# SCH_ChaserPCB_2025-10-18.net
KiCad netlist of a schematic drawn in EasyEDA
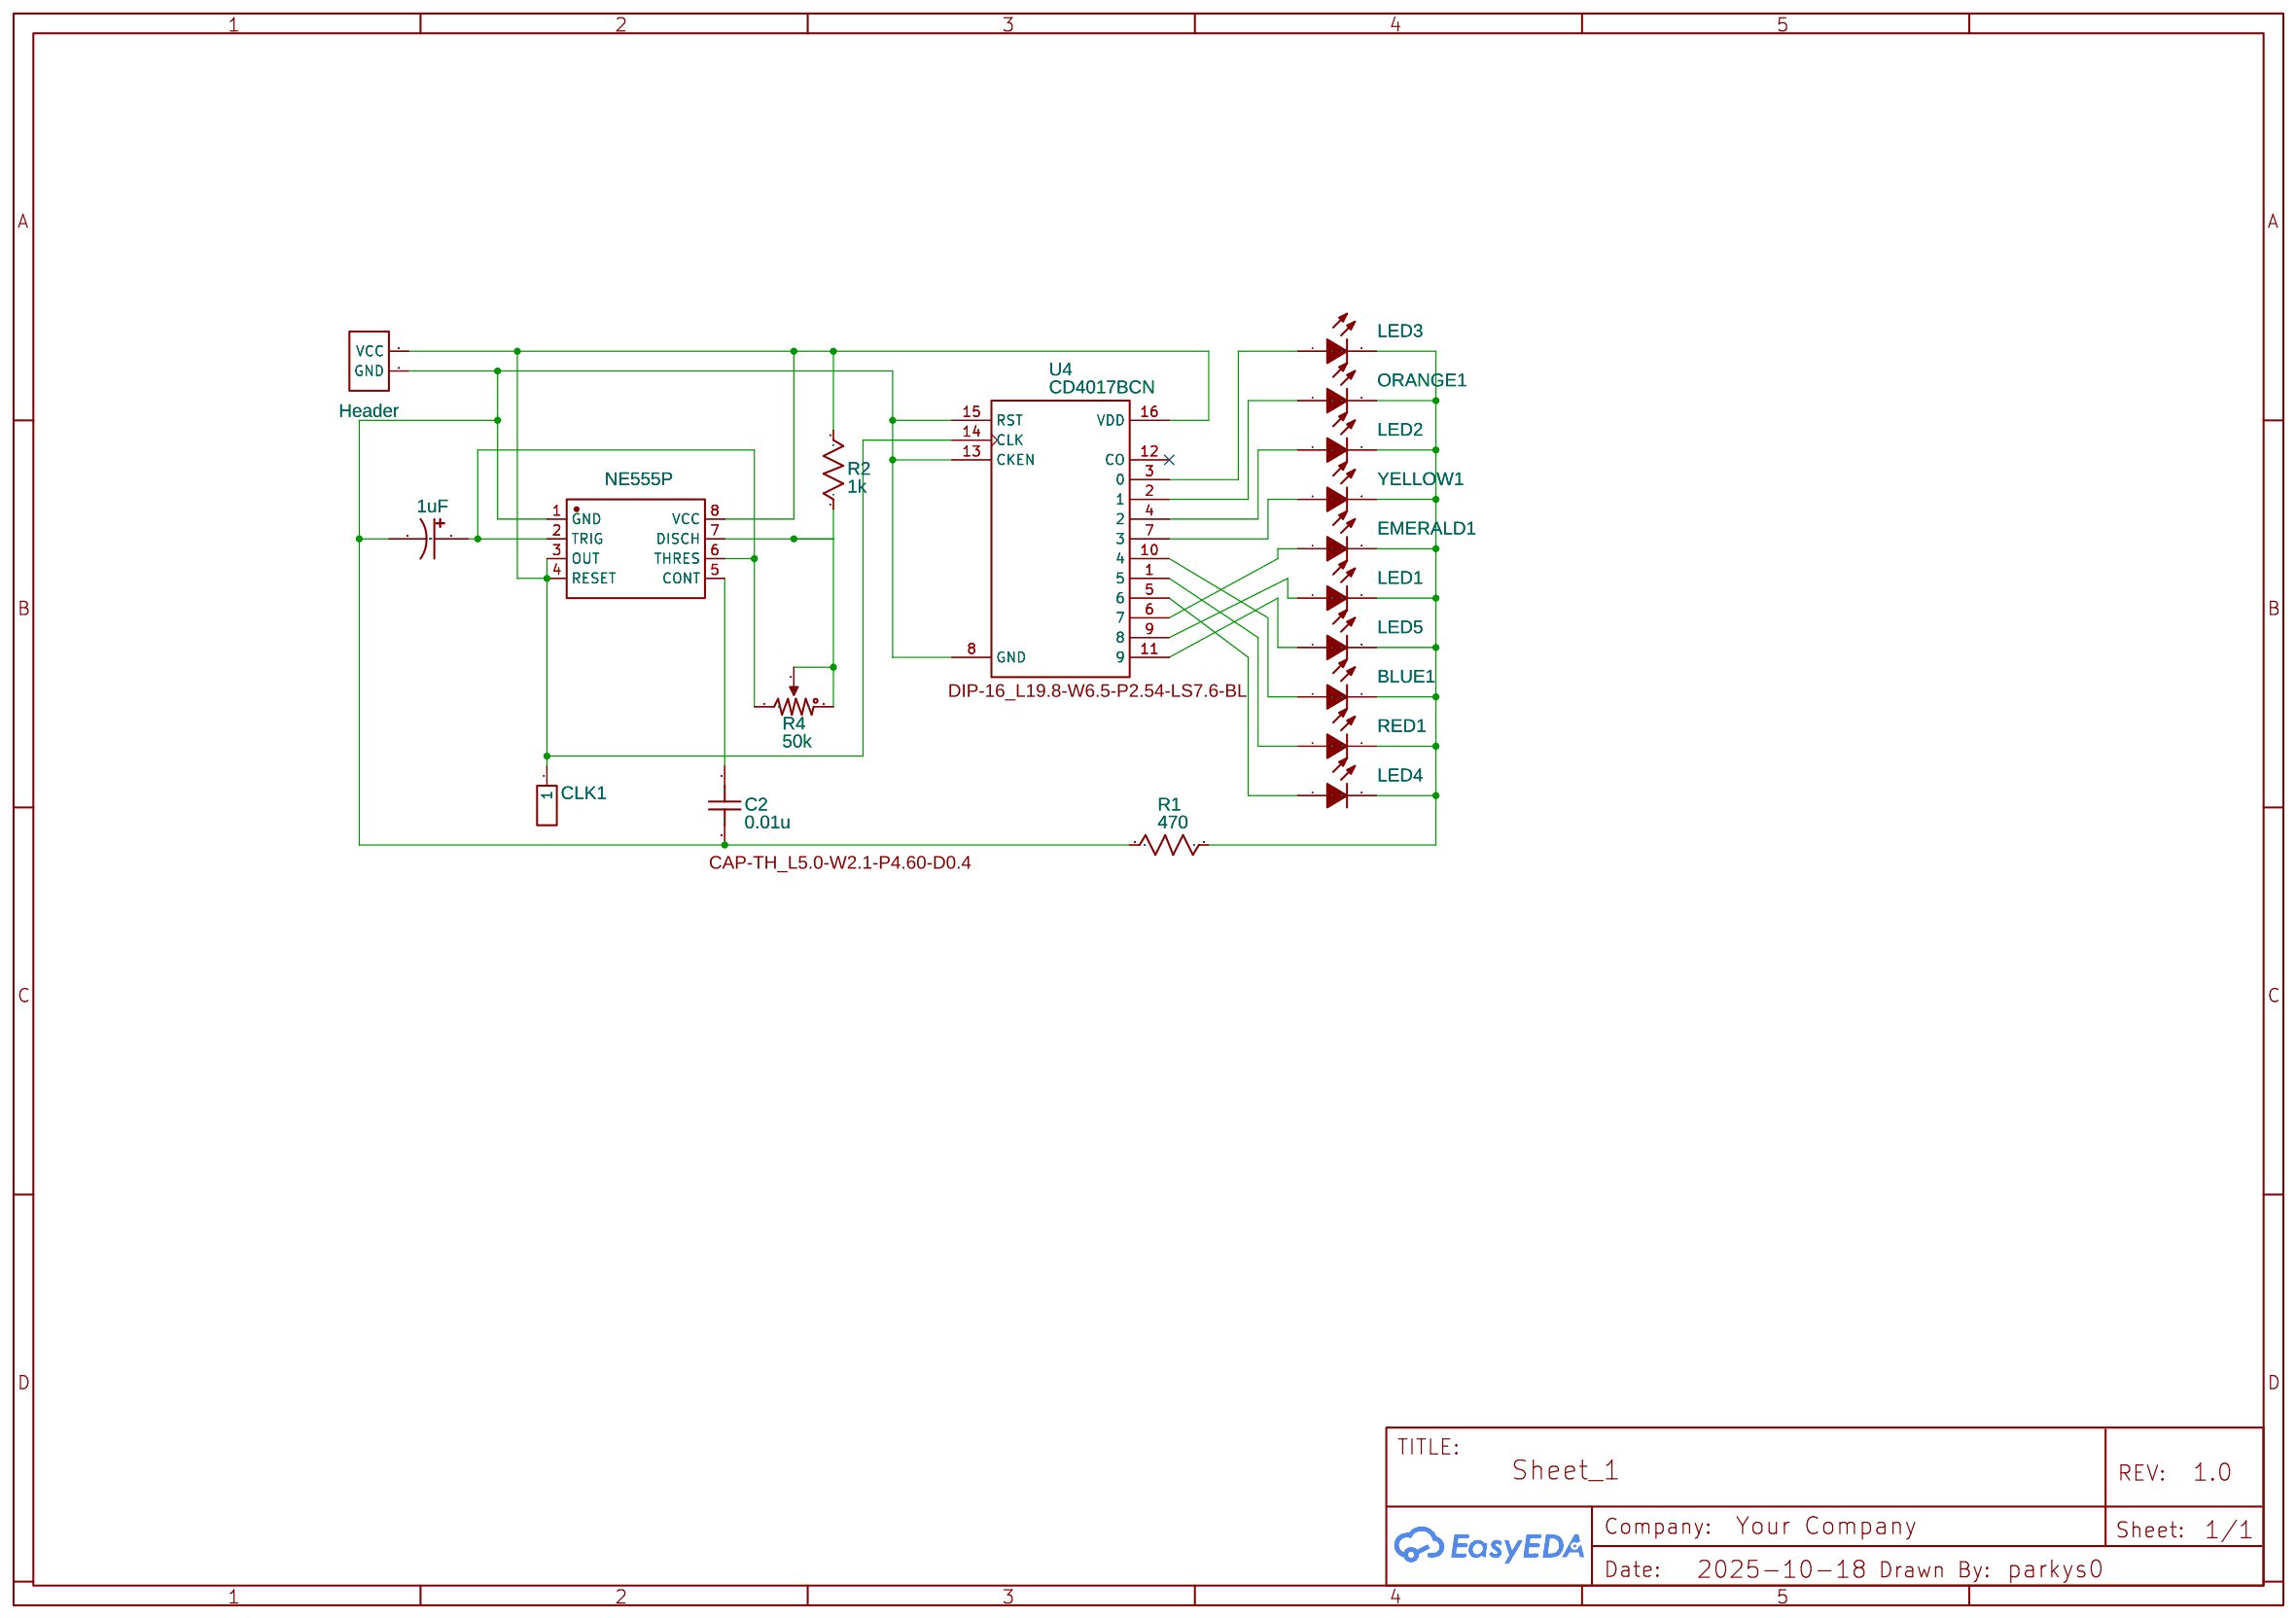
[diagram p0: schematic sheet]

(export (version "E")
  (design (tool "Eeschema 10.0.6"))
  (components
    (comp (ref "BLUE1") (value "LED_5MM") (libsource (lib "") (part "LED_5MM_1")))
    (comp (ref "C1")
      (value "1uF")
      (fields (field (name "Manufacturer Part") "UVZ1H010MDD") (field (name "Manufacturer") "Nichicon(尼吉康)"))
      (libsource (lib "") (part "UVZ1H010MDD"))
    )
    (comp (ref "C2") (value "0.01u") (libsource (lib "") (part "C_0603_US")))
    (comp (ref "CLK1")
      (value "C81276")
      (fields
        (field (name "Manufacturer Part") "2.54-1*1P针")
        (field (name "Manufacturer") "BOOMELE(Boom Precision Elec)")
      )
      (libsource (lib "") (part "Header-Male-2.54_1x1"))
    )
    (comp (ref "EMERALD1") (value "LED_5MM") (libsource (lib "") (part "LED_5MM_4")))
    (comp (ref "H1") (value "Header") (libsource (lib "") (part "HEADER-FEMALE-2.54_1X2")))
    (comp (ref "LED1") (value "LED_5MM") (libsource (lib "") (part "LED_5MM")))
    (comp (ref "LED2") (value "LED_5MM") (libsource (lib "") (part "LED_5MM")))
    (comp (ref "LED3") (value "LED_5MM") (libsource (lib "") (part "LED_5MM")))
    (comp (ref "LED4") (value "LED_5MM") (libsource (lib "") (part "LED_5MM")))
    (comp (ref "LED5") (value "LED_5MM") (libsource (lib "") (part "LED_5MM")))
    (comp (ref "ORANGE1") (value "LED_5MM") (libsource (lib "") (part "LED_5MM_5")))
    (comp (ref "R1")
      (value "470")
      (fields (field (name "Manufacturer Part") "?"))
      (libsource (lib "") (part "Resistor"))
    )
    (comp (ref "R2")
      (value "1k")
      (fields (field (name "Manufacturer Part") "?"))
      (libsource (lib "") (part "Resistor_1"))
    )
    (comp (ref "R4")
      (value "50k")
      (fields (field (name "Manufacturer Part") "?"))
      (libsource (lib "") (part "Potentiometer"))
    )
    (comp (ref "RED1") (value "LED_5MM") (libsource (lib "") (part "LED_5MM_2")))
    (comp (ref "U2")
      (value "NE555P")
      (fields (field (name "Manufacturer") "TI(德州仪器)"))
      (libsource (lib "") (part "NE555P"))
    )
    (comp (ref "U4") (value "CD4017BCN") (libsource (lib "") (part "CD4017BCN")))
    (comp (ref "YELLOW1") (value "LED_5MM") (libsource (lib "") (part "LED_5MM_3")))
  )
  (nets
    (net (code "1") (name "Net-(BLUE1-A)") (class "Default")
      (node (ref "BLUE1") (pin "1") (pinfunction "A_1") (pintype "input"))
      (node (ref "U4") (pin "10") (pinfunction "4_10") (pintype "output"))
    )
    (net (code "2") (name "Net-(BLUE1-K)") (class "Default")
      (node (ref "BLUE1") (pin "2") (pinfunction "K_2") (pintype "input"))
      (node (ref "EMERALD1") (pin "2") (pinfunction "K_2") (pintype "input"))
      (node (ref "LED1") (pin "2") (pinfunction "K_2") (pintype "input"))
      (node (ref "LED2") (pin "2") (pinfunction "K_2") (pintype "input"))
      (node (ref "LED3") (pin "2") (pinfunction "K_2") (pintype "input"))
      (node (ref "LED4") (pin "2") (pinfunction "K_2") (pintype "input"))
      (node (ref "LED5") (pin "2") (pinfunction "K_2") (pintype "input"))
      (node (ref "ORANGE1") (pin "2") (pinfunction "K_2") (pintype "input"))
      (node (ref "R1") (pin "1") (pinfunction "1_1") (pintype "unspecified"))
      (node (ref "RED1") (pin "2") (pinfunction "K_2") (pintype "input"))
      (node (ref "YELLOW1") (pin "2") (pinfunction "K_2") (pintype "input"))
    )
    (net (code "3") (name "Net-(EMERALD1-A)") (class "Default")
      (node (ref "EMERALD1") (pin "1") (pinfunction "A_1") (pintype "input"))
      (node (ref "U4") (pin "6") (pinfunction "7_6") (pintype "output"))
    )
    (net (code "4") (name "Net-(H1-GND)") (class "Default")
      (node (ref "C1") (pin "2") (pinfunction "2_2") (pintype "unspecified"))
      (node (ref "C2") (pin "2") (pinfunction "2_2") (pintype "unspecified"))
      (node (ref "H1") (pin "2") (pinfunction "GND_2") (pintype "unspecified"))
      (node (ref "R1") (pin "2") (pinfunction "2_2") (pintype "unspecified"))
      (node (ref "U2") (pin "1") (pinfunction "GND_1") (pintype "unspecified"))
      (node (ref "U4") (pin "13") (pinfunction "CKEN_13") (pintype "unspecified"))
      (node (ref "U4") (pin "15") (pinfunction "RST_15") (pintype "unspecified"))
      (node (ref "U4") (pin "8") (pinfunction "GND_8") (pintype "passive"))
    )
    (net (code "5") (name "Net-(H1-VCC)") (class "Default")
      (node (ref "CLK1") (pin "1") (pinfunction "1_1") (pintype "unspecified"))
      (node (ref "H1") (pin "1") (pinfunction "VCC_1") (pintype "unspecified"))
      (node (ref "R2") (pin "2") (pinfunction "2_2") (pintype "unspecified"))
      (node (ref "U2") (pin "3") (pinfunction "OUT_3") (pintype "unspecified"))
      (node (ref "U2") (pin "4") (pinfunction "RESET_4") (pintype "unspecified"))
      (node (ref "U2") (pin "8") (pinfunction "VCC_8") (pintype "unspecified"))
      (node (ref "U4") (pin "14") (pinfunction "CLK_14") (pintype "unspecified"))
      (node (ref "U4") (pin "16") (pinfunction "VDD_16") (pintype "passive"))
    )
    (net (code "6") (name "Net-(LED1-A)") (class "Default")
      (node (ref "LED1") (pin "1") (pinfunction "A_1") (pintype "input"))
      (node (ref "U4") (pin "9") (pinfunction "8_9") (pintype "output"))
    )
    (net (code "7") (name "Net-(LED2-A)") (class "Default")
      (node (ref "LED2") (pin "1") (pinfunction "A_1") (pintype "input"))
      (node (ref "U4") (pin "4") (pinfunction "2_4") (pintype "output"))
    )
    (net (code "8") (name "Net-(LED3-A)") (class "Default")
      (node (ref "LED3") (pin "1") (pinfunction "A_1") (pintype "input"))
      (node (ref "U4") (pin "3") (pinfunction "0_3") (pintype "output"))
    )
    (net (code "9") (name "Net-(LED4-A)") (class "Default")
      (node (ref "LED4") (pin "1") (pinfunction "A_1") (pintype "input"))
      (node (ref "U4") (pin "5") (pinfunction "6_5") (pintype "output"))
    )
    (net (code "10") (name "Net-(LED5-A)") (class "Default")
      (node (ref "LED5") (pin "1") (pinfunction "A_1") (pintype "input"))
      (node (ref "U4") (pin "11") (pinfunction "9_11") (pintype "output"))
    )
    (net (code "11") (name "Net-(ORANGE1-A)") (class "Default")
      (node (ref "ORANGE1") (pin "1") (pinfunction "A_1") (pintype "input"))
      (node (ref "U4") (pin "2") (pinfunction "1_2") (pintype "output"))
    )
    (net (code "12") (name "Net-(R4-2)") (class "Default")
      (node (ref "R2") (pin "1") (pinfunction "1_1") (pintype "unspecified"))
      (node (ref "R4") (pin "2") (pinfunction "3_2") (pintype "unspecified"))
      (node (ref "R4") (pin "3") (pinfunction "2_3") (pintype "unspecified"))
      (node (ref "U2") (pin "7") (pinfunction "DISCH_7") (pintype "unspecified"))
    )
    (net (code "13") (name "Net-(RED1-A)") (class "Default")
      (node (ref "RED1") (pin "1") (pinfunction "A_1") (pintype "input"))
      (node (ref "U4") (pin "1") (pinfunction "5_1") (pintype "output"))
    )
    (net (code "14") (name "Net-(U2-CONT)") (class "Default")
      (node (ref "C2") (pin "1") (pinfunction "1_1") (pintype "unspecified"))
      (node (ref "U2") (pin "5") (pinfunction "CONT_5") (pintype "unspecified"))
    )
    (net (code "15") (name "Net-(U2-THRES)") (class "Default")
      (node (ref "C1") (pin "1") (pinfunction "1_1") (pintype "unspecified"))
      (node (ref "R4") (pin "1") (pinfunction "1_1") (pintype "unspecified"))
      (node (ref "U2") (pin "2") (pinfunction "TRIG_2") (pintype "unspecified"))
      (node (ref "U2") (pin "6") (pinfunction "THRES_6") (pintype "unspecified"))
    )
    (net (code "16") (name "Net-(U4-3)") (class "Default")
      (node (ref "U4") (pin "7") (pinfunction "3_7") (pintype "output"))
      (node (ref "YELLOW1") (pin "1") (pinfunction "A_1") (pintype "input"))
    )
    (net (code "17") (name "unconnected-(U4-CO-Pad12)") (class "Default")
      (node (ref "U4") (pin "12") (pinfunction "CO_12") (pintype "output+no_connect"))
    )
  )
)
